# pwr.net
KiCad netlist of a schematic drawn in Altium Designer
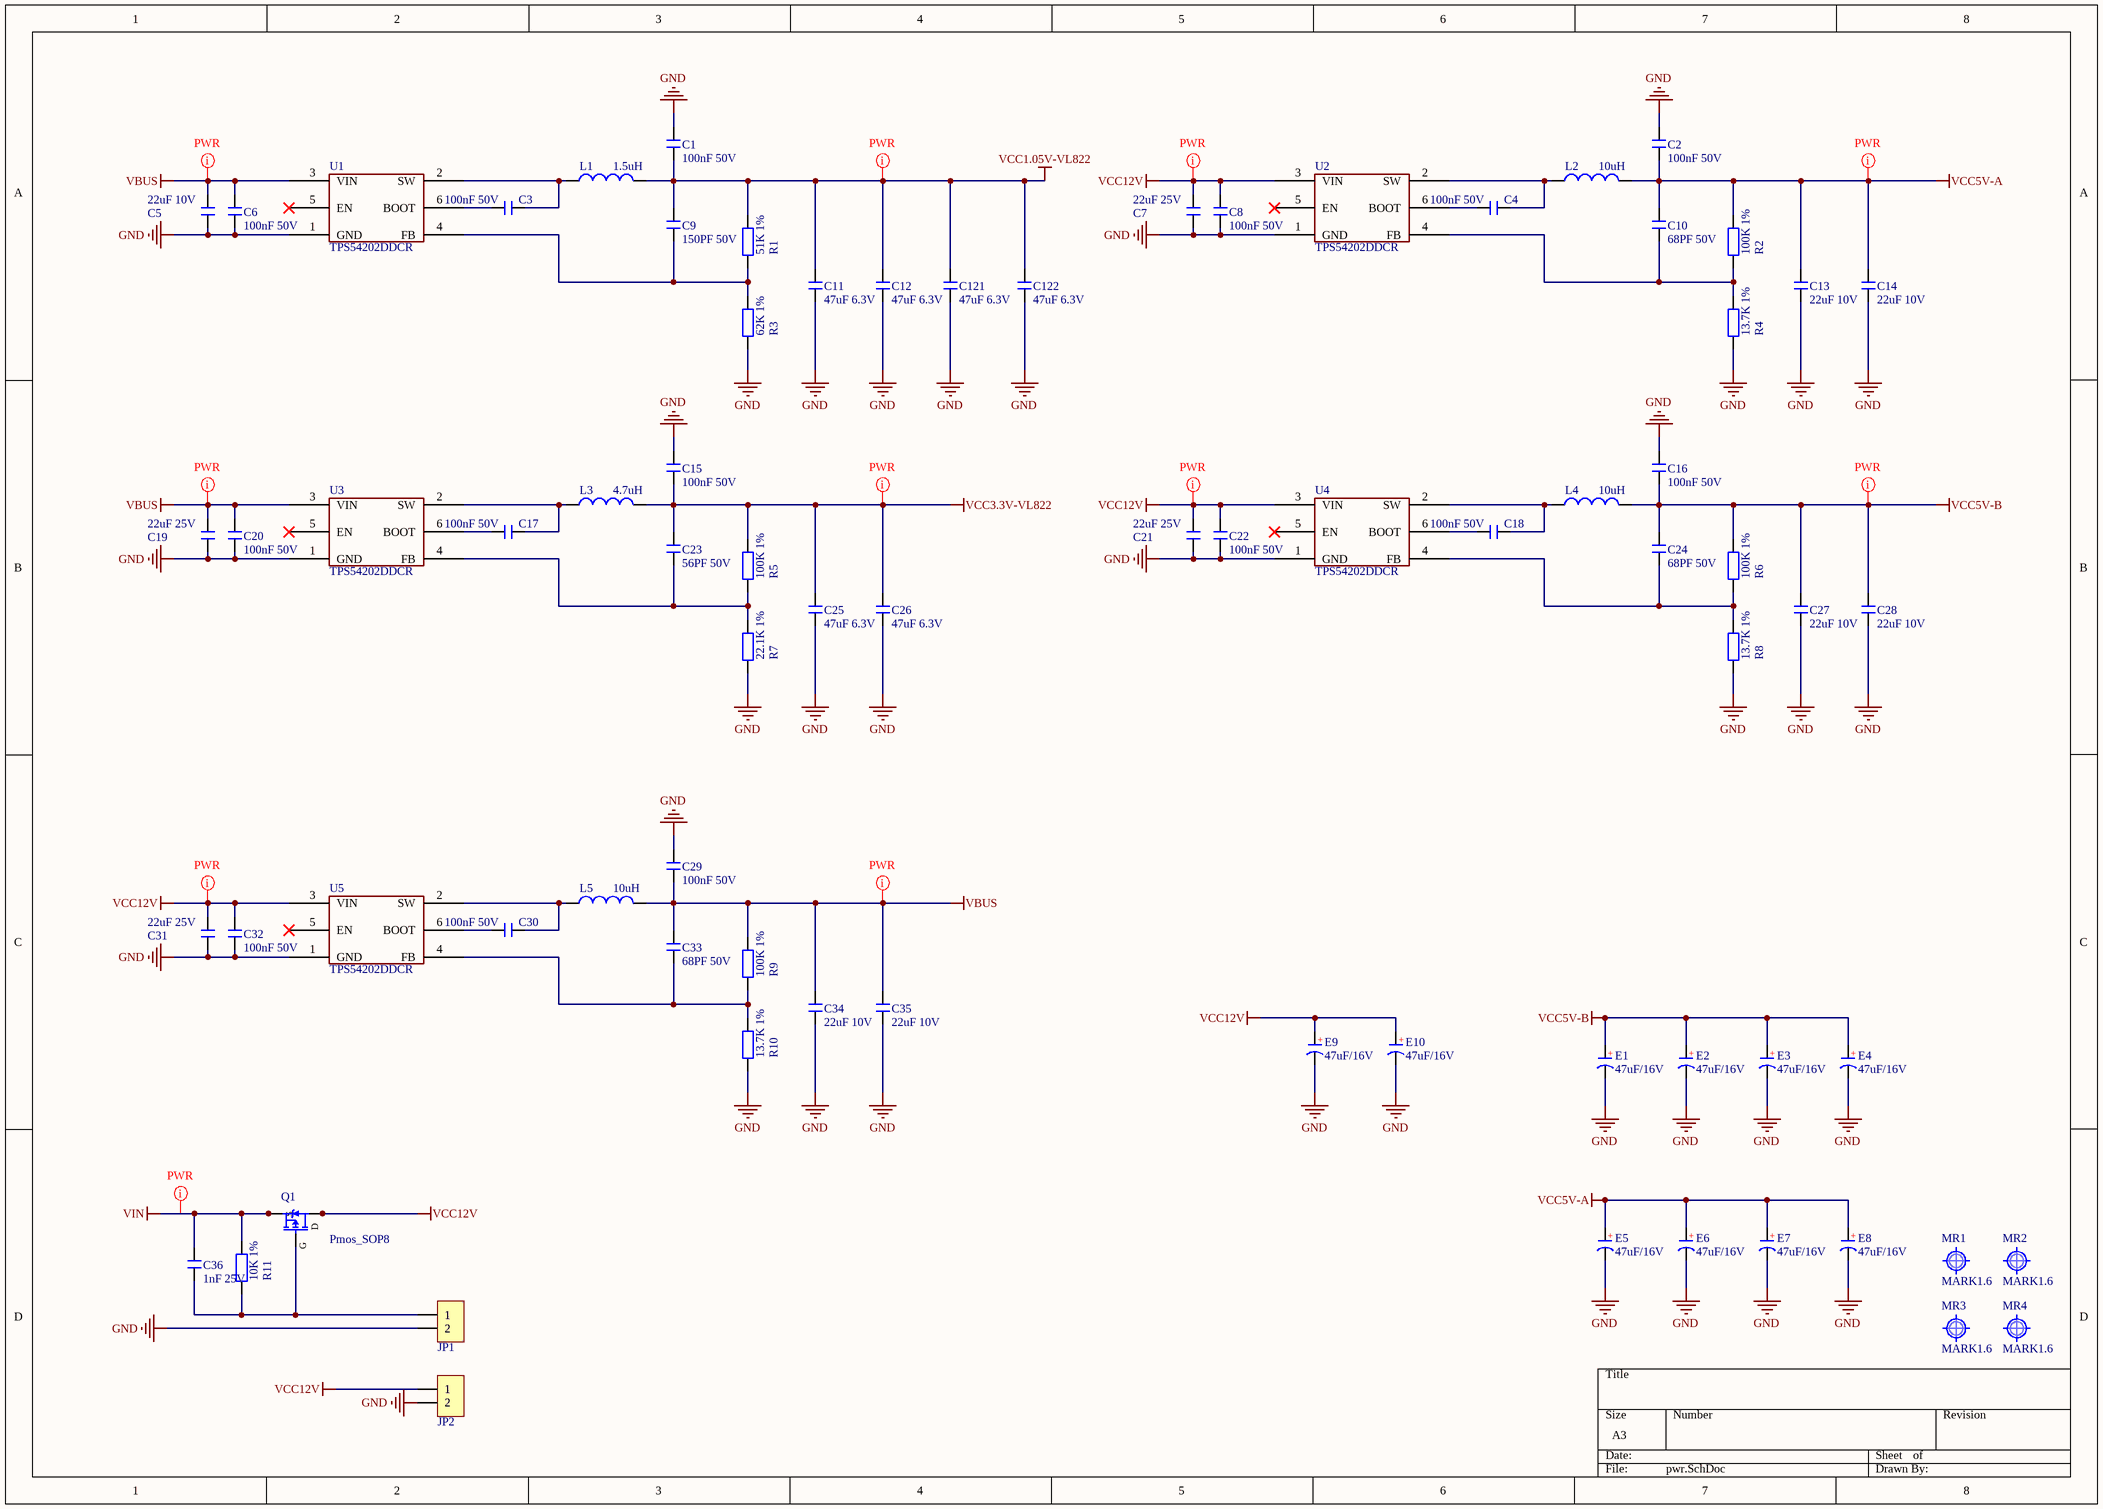
[diagram p0: pwr.SchDoc]

(export (version "E")
  (design (tool "Eeschema 10.0.6"))
  (components
    (comp (ref "C1")
      (value "100nF 50V")
      (footprint "C0402_L")
      (description "无极性贴片电容")
      (fields (field (name "版权归属") "源创客"))
      (libsource (lib "Capacitor") (part "C"))
    )
    (comp (ref "C2")
      (value "100nF 50V")
      (footprint "C0402_L")
      (description "无极性贴片电容")
      (fields (field (name "版权归属") "源创客"))
      (libsource (lib "Capacitor") (part "C"))
    )
    (comp (ref "C3")
      (value "100nF 50V")
      (footprint "C0402_L")
      (description "无极性贴片电容")
      (fields (field (name "版权归属") "源创客"))
      (libsource (lib "Capacitor") (part "C"))
    )
    (comp (ref "C4")
      (value "100nF 50V")
      (footprint "C0402_L")
      (description "无极性贴片电容")
      (fields (field (name "版权归属") "源创客"))
      (libsource (lib "Capacitor") (part "C"))
    )
    (comp (ref "C5")
      (value "22uF 10V")
      (footprint "C0805_L")
      (description "无极性贴片电容")
      (fields (field (name "版权归属") "源创客"))
      (libsource (lib "Capacitor") (part "C"))
    )
    (comp (ref "C6")
      (value "100nF 50V")
      (footprint "C0402_L")
      (description "无极性贴片电容")
      (fields (field (name "版权归属") "源创客"))
      (libsource (lib "Capacitor") (part "C"))
    )
    (comp (ref "C7")
      (value "22uF 25V")
      (footprint "C0805_L")
      (description "无极性贴片电容")
      (fields (field (name "版权归属") "源创客"))
      (libsource (lib "Capacitor") (part "C"))
    )
    (comp (ref "C8")
      (value "100nF 50V")
      (footprint "C0402_L")
      (description "无极性贴片电容")
      (fields (field (name "版权归属") "源创客"))
      (libsource (lib "Capacitor") (part "C"))
    )
    (comp (ref "C9")
      (value "150PF 50V")
      (footprint "C0402_L")
      (description "无极性贴片电容")
      (fields (field (name "版权归属") "源创客"))
      (libsource (lib "Capacitor") (part "C"))
    )
    (comp (ref "C10")
      (value "68PF 50V")
      (footprint "C0402_L")
      (description "无极性贴片电容")
      (fields (field (name "版权归属") "源创客"))
      (libsource (lib "Capacitor") (part "C"))
    )
    (comp (ref "C11")
      (value "47uF 6.3V")
      (footprint "C0805_L")
      (description "无极性贴片电容")
      (fields (field (name "版权归属") "源创客"))
      (libsource (lib "Capacitor") (part "C"))
    )
    (comp (ref "C12")
      (value "47uF 6.3V")
      (footprint "C0805_L")
      (description "无极性贴片电容")
      (fields (field (name "版权归属") "源创客"))
      (libsource (lib "Capacitor") (part "C"))
    )
    (comp (ref "C13")
      (value "22uF 10V")
      (footprint "C0805_L")
      (description "无极性贴片电容")
      (fields (field (name "版权归属") "源创客"))
      (libsource (lib "Capacitor") (part "C"))
    )
    (comp (ref "C14")
      (value "22uF 10V")
      (footprint "C0805_L")
      (description "无极性贴片电容")
      (fields (field (name "版权归属") "源创客"))
      (libsource (lib "Capacitor") (part "C"))
    )
    (comp (ref "C15")
      (value "100nF 50V")
      (footprint "C0402_L")
      (description "无极性贴片电容")
      (fields (field (name "版权归属") "源创客"))
      (libsource (lib "Capacitor") (part "C"))
    )
    (comp (ref "C16")
      (value "100nF 50V")
      (footprint "C0402_L")
      (description "无极性贴片电容")
      (fields (field (name "版权归属") "源创客"))
      (libsource (lib "Capacitor") (part "C"))
    )
    (comp (ref "C17")
      (value "100nF 50V")
      (footprint "C0402_L")
      (description "无极性贴片电容")
      (fields (field (name "版权归属") "源创客"))
      (libsource (lib "Capacitor") (part "C"))
    )
    (comp (ref "C18")
      (value "100nF 50V")
      (footprint "C0402_L")
      (description "无极性贴片电容")
      (fields (field (name "版权归属") "源创客"))
      (libsource (lib "Capacitor") (part "C"))
    )
    (comp (ref "C19")
      (value "22uF 25V")
      (footprint "C0805_L")
      (description "无极性贴片电容")
      (fields (field (name "版权归属") "源创客"))
      (libsource (lib "Capacitor") (part "C"))
    )
    (comp (ref "C20")
      (value "100nF 50V")
      (footprint "C0402_L")
      (description "无极性贴片电容")
      (fields (field (name "版权归属") "源创客"))
      (libsource (lib "Capacitor") (part "C"))
    )
    (comp (ref "C21")
      (value "22uF 25V")
      (footprint "C0805_L")
      (description "无极性贴片电容")
      (fields (field (name "版权归属") "源创客"))
      (libsource (lib "Capacitor") (part "C"))
    )
    (comp (ref "C22")
      (value "100nF 50V")
      (footprint "C0402_L")
      (description "无极性贴片电容")
      (fields (field (name "版权归属") "源创客"))
      (libsource (lib "Capacitor") (part "C"))
    )
    (comp (ref "C23")
      (value "56PF 50V")
      (footprint "C0402_L")
      (description "无极性贴片电容")
      (fields (field (name "版权归属") "源创客"))
      (libsource (lib "Capacitor") (part "C"))
    )
    (comp (ref "C24")
      (value "68PF 50V")
      (footprint "C0402_L")
      (description "无极性贴片电容")
      (fields (field (name "版权归属") "源创客"))
      (libsource (lib "Capacitor") (part "C"))
    )
    (comp (ref "C25")
      (value "47uF 6.3V")
      (footprint "C0805_L")
      (description "无极性贴片电容")
      (fields (field (name "版权归属") "源创客"))
      (libsource (lib "Capacitor") (part "C"))
    )
    (comp (ref "C26")
      (value "47uF 6.3V")
      (footprint "C0805_L")
      (description "无极性贴片电容")
      (fields (field (name "版权归属") "源创客"))
      (libsource (lib "Capacitor") (part "C"))
    )
    (comp (ref "C27")
      (value "22uF 10V")
      (footprint "C0805_L")
      (description "无极性贴片电容")
      (fields (field (name "版权归属") "源创客"))
      (libsource (lib "Capacitor") (part "C"))
    )
    (comp (ref "C28")
      (value "22uF 10V")
      (footprint "C0805_L")
      (description "无极性贴片电容")
      (fields (field (name "版权归属") "源创客"))
      (libsource (lib "Capacitor") (part "C"))
    )
    (comp (ref "C29")
      (value "100nF 50V")
      (footprint "C0402_L")
      (description "无极性贴片电容")
      (fields (field (name "版权归属") "源创客"))
      (libsource (lib "Capacitor") (part "C"))
    )
    (comp (ref "C30")
      (value "100nF 50V")
      (footprint "C0402_L")
      (description "无极性贴片电容")
      (fields (field (name "版权归属") "源创客"))
      (libsource (lib "Capacitor") (part "C"))
    )
    (comp (ref "C31")
      (value "22uF 25V")
      (footprint "C0805_L")
      (description "无极性贴片电容")
      (fields (field (name "版权归属") "源创客"))
      (libsource (lib "Capacitor") (part "C"))
    )
    (comp (ref "C32")
      (value "100nF 50V")
      (footprint "C0402_L")
      (description "无极性贴片电容")
      (fields (field (name "版权归属") "源创客"))
      (libsource (lib "Capacitor") (part "C"))
    )
    (comp (ref "C33")
      (value "68PF 50V")
      (footprint "C0402_L")
      (description "无极性贴片电容")
      (fields (field (name "版权归属") "源创客"))
      (libsource (lib "Capacitor") (part "C"))
    )
    (comp (ref "C34")
      (value "22uF 10V")
      (footprint "C0805_L")
      (description "无极性贴片电容")
      (fields (field (name "版权归属") "源创客"))
      (libsource (lib "Capacitor") (part "C"))
    )
    (comp (ref "C35")
      (value "22uF 10V")
      (footprint "C0805_L")
      (description "无极性贴片电容")
      (fields (field (name "版权归属") "源创客"))
      (libsource (lib "Capacitor") (part "C"))
    )
    (comp (ref "C36")
      (value "1nF 25V")
      (footprint "C0402_L")
      (description "无极性贴片电容")
      (fields (field (name "版权归属") "源创客"))
      (libsource (lib "Capacitor") (part "C"))
    )
    (comp (ref "C121")
      (value "47uF 6.3V")
      (footprint "C0805_L")
      (description "无极性贴片电容")
      (fields (field (name "版权归属") "源创客"))
      (libsource (lib "Capacitor") (part "C"))
    )
    (comp (ref "C122")
      (value "47uF 6.3V")
      (footprint "C0805_L")
      (description "无极性贴片电容")
      (fields (field (name "版权归属") "源创客"))
      (libsource (lib "Capacitor") (part "C"))
    )
    (comp (ref "E1")
      (value "47uF/16V")
      (footprint "CS 6*4 - R")
      (description "贴片电解电容")
      (fields (field (name "版权归属") "源创客"))
      (libsource (lib "Capacitor") (part "C-CD"))
    )
    (comp (ref "E2")
      (value "47uF/16V")
      (footprint "CS 6*4 - R")
      (description "贴片电解电容")
      (fields (field (name "版权归属") "源创客"))
      (libsource (lib "Capacitor") (part "C-CD"))
    )
    (comp (ref "E3")
      (value "47uF/16V")
      (footprint "CS 6*4 - R")
      (description "贴片电解电容")
      (fields (field (name "版权归属") "源创客"))
      (libsource (lib "Capacitor") (part "C-CD"))
    )
    (comp (ref "E4")
      (value "47uF/16V")
      (footprint "CS 6*4 - R")
      (description "贴片电解电容")
      (fields (field (name "版权归属") "源创客"))
      (libsource (lib "Capacitor") (part "C-CD"))
    )
    (comp (ref "E5")
      (value "47uF/16V")
      (footprint "CS 6*4 - R")
      (description "贴片电解电容")
      (fields (field (name "版权归属") "源创客"))
      (libsource (lib "Capacitor") (part "C-CD"))
    )
    (comp (ref "E6")
      (value "47uF/16V")
      (footprint "CS 6*4 - R")
      (description "贴片电解电容")
      (fields (field (name "版权归属") "源创客"))
      (libsource (lib "Capacitor") (part "C-CD"))
    )
    (comp (ref "E7")
      (value "47uF/16V")
      (footprint "CS 6*4 - R")
      (description "贴片电解电容")
      (fields (field (name "版权归属") "源创客"))
      (libsource (lib "Capacitor") (part "C-CD"))
    )
    (comp (ref "E8")
      (value "47uF/16V")
      (footprint "CS 6*4 - R")
      (description "贴片电解电容")
      (fields (field (name "版权归属") "源创客"))
      (libsource (lib "Capacitor") (part "C-CD"))
    )
    (comp (ref "E9")
      (value "47uF/16V")
      (footprint "CS 6*4 - R")
      (description "贴片电解电容")
      (fields (field (name "版权归属") "源创客"))
      (libsource (lib "Capacitor") (part "C-CD"))
    )
    (comp (ref "E10")
      (value "47uF/16V")
      (footprint "CS 6*4 - R")
      (description "贴片电解电容")
      (fields (field (name "版权归属") "源创客"))
      (libsource (lib "Capacitor") (part "C-CD"))
    )
    (comp (ref "JP1")
      (value "HDR-1X2")
      (footprint "ZH1.5-WS-2P")
      (description "2P接插件")
      (fields (field (name "版权归属") "源创客"))
      (libsource (lib "Connector-PinHeader") (part "Header 2"))
    )
    (comp (ref "JP2")
      (value "HDR-1X2")
      (footprint "XH2.54-WS-2P")
      (description "2P接插件")
      (fields (field (name "版权归属") "源创客"))
      (libsource (lib "Connector-PinHeader") (part "Header 2"))
    )
    (comp (ref "L1")
      (value "1.5uH")
      (footprint "SMMS0420")
      (description "小功率贴片电感")
      (fields (field (name "版权归属") "源创客"))
      (libsource (lib "Inductor") (part "L"))
    )
    (comp (ref "L2")
      (value "10uH")
      (footprint "SMMS0420")
      (description "小功率贴片电感")
      (fields (field (name "版权归属") "源创客"))
      (libsource (lib "Inductor") (part "L"))
    )
    (comp (ref "L3")
      (value "4.7uH")
      (footprint "SMMS0420")
      (description "小功率贴片电感")
      (fields (field (name "版权归属") "源创客"))
      (libsource (lib "Inductor") (part "L"))
    )
    (comp (ref "L4")
      (value "10uH")
      (footprint "SMMS0420")
      (description "小功率贴片电感")
      (fields (field (name "版权归属") "源创客"))
      (libsource (lib "Inductor") (part "L"))
    )
    (comp (ref "L5")
      (value "10uH")
      (footprint "SMMS0420")
      (description "小功率贴片电感")
      (fields (field (name "版权归属") "源创客"))
      (libsource (lib "Inductor") (part "L"))
    )
    (comp (ref "MR1")
      (value "MARK1.6")
      (footprint "Mark 1")
      (description "光学定位点")
      (fields (field (name "版权归属") "源创客"))
      (libsource (lib "Hole") (part "MARK"))
    )
    (comp (ref "MR2")
      (value "MARK1.6")
      (footprint "Mark 1")
      (description "光学定位点")
      (fields (field (name "版权归属") "源创客"))
      (libsource (lib "Hole") (part "MARK"))
    )
    (comp (ref "MR3")
      (value "MARK1.6")
      (footprint "Mark 1")
      (description "光学定位点")
      (fields (field (name "版权归属") "源创客"))
      (libsource (lib "Hole") (part "MARK"))
    )
    (comp (ref "MR4")
      (value "MARK1.6")
      (footprint "Mark 1")
      (description "光学定位点")
      (fields (field (name "版权归属") "源创客"))
      (libsource (lib "Hole") (part "MARK"))
    )
    (comp (ref "Q1")
      (value "Pmos_SOP8")
      (footprint "SOP8_L")
      (fields (field (name "版权归属") "源创客"))
      (libsource (lib "MOSFET BJT IGBT") (part "Pmos_SOP8"))
    )
    (comp (ref "R1")
      (value "51K 1%")
      (footprint "R0402_L")
      (description "贴片电阻")
      (fields (field (name "版权归属") "源创客"))
      (libsource (lib "Resistor") (part "R"))
    )
    (comp (ref "R2")
      (value "100K 1%")
      (footprint "R0402_L")
      (description "贴片电阻")
      (fields (field (name "版权归属") "源创客"))
      (libsource (lib "Resistor") (part "R"))
    )
    (comp (ref "R3")
      (value "62K 1%")
      (footprint "R0402_L")
      (description "贴片电阻")
      (fields (field (name "版权归属") "源创客"))
      (libsource (lib "Resistor") (part "R"))
    )
    (comp (ref "R4")
      (value "13.7K 1%")
      (footprint "R0402_L")
      (description "贴片电阻")
      (fields (field (name "版权归属") "源创客"))
      (libsource (lib "Resistor") (part "R"))
    )
    (comp (ref "R5")
      (value "100K 1%")
      (footprint "R0402_L")
      (description "贴片电阻")
      (fields (field (name "版权归属") "源创客"))
      (libsource (lib "Resistor") (part "R"))
    )
    (comp (ref "R6")
      (value "100K 1%")
      (footprint "R0402_L")
      (description "贴片电阻")
      (fields (field (name "版权归属") "源创客"))
      (libsource (lib "Resistor") (part "R"))
    )
    (comp (ref "R7")
      (value "22.1K 1%")
      (footprint "R0402_L")
      (description "贴片电阻")
      (fields (field (name "版权归属") "源创客"))
      (libsource (lib "Resistor") (part "R"))
    )
    (comp (ref "R8")
      (value "13.7K 1%")
      (footprint "R0402_L")
      (description "贴片电阻")
      (fields (field (name "版权归属") "源创客"))
      (libsource (lib "Resistor") (part "R"))
    )
    (comp (ref "R9")
      (value "100K 1%")
      (footprint "R0402_L")
      (description "贴片电阻")
      (fields (field (name "版权归属") "源创客"))
      (libsource (lib "Resistor") (part "R"))
    )
    (comp (ref "R10")
      (value "13.7K 1%")
      (footprint "R0402_L")
      (description "贴片电阻")
      (fields (field (name "版权归属") "源创客"))
      (libsource (lib "Resistor") (part "R"))
    )
    (comp (ref "R11")
      (value "10K 1%")
      (footprint "R0402_L")
      (description "贴片电阻")
      (fields (field (name "版权归属") "源创客"))
      (libsource (lib "Resistor") (part "R"))
    )
    (comp (ref "U1")
      (value "TPS54202DDCR")
      (footprint "SOT23-6L")
      (description "DCDC Convert")
      (libsource (lib "DCDC Convert") (part "TPS54202DDCR"))
    )
    (comp (ref "U2")
      (value "TPS54202DDCR")
      (footprint "SOT23-6L")
      (description "DCDC Convert")
      (libsource (lib "DCDC Convert") (part "TPS54202DDCR"))
    )
    (comp (ref "U3")
      (value "TPS54202DDCR")
      (footprint "SOT23-6L")
      (description "DCDC Convert")
      (libsource (lib "DCDC Convert") (part "TPS54202DDCR"))
    )
    (comp (ref "U4")
      (value "TPS54202DDCR")
      (footprint "SOT23-6L")
      (description "DCDC Convert")
      (libsource (lib "DCDC Convert") (part "TPS54202DDCR"))
    )
    (comp (ref "U5")
      (value "TPS54202DDCR")
      (footprint "SOT23-6L")
      (description "DCDC Convert")
      (libsource (lib "DCDC Convert") (part "TPS54202DDCR"))
    )
  )
  (nets
    (net (code "1") (name "GND") (class "Default")
      (node (ref "C1") (pin "2") (pinfunction "2_2") (pintype "passive"))
      (node (ref "C11") (pin "2") (pinfunction "2_2") (pintype "passive"))
      (node (ref "C12") (pin "2") (pinfunction "2_2") (pintype "passive"))
      (node (ref "C121") (pin "2") (pinfunction "2_2") (pintype "passive"))
      (node (ref "C122") (pin "2") (pinfunction "2_2") (pintype "passive"))
      (node (ref "C13") (pin "2") (pinfunction "2_2") (pintype "passive"))
      (node (ref "C14") (pin "2") (pinfunction "2_2") (pintype "passive"))
      (node (ref "C15") (pin "2") (pinfunction "2_2") (pintype "passive"))
      (node (ref "C16") (pin "2") (pinfunction "2_2") (pintype "passive"))
      (node (ref "C19") (pin "1") (pinfunction "1_1") (pintype "passive"))
      (node (ref "C2") (pin "2") (pinfunction "2_2") (pintype "passive"))
      (node (ref "C20") (pin "1") (pinfunction "1_1") (pintype "passive"))
      (node (ref "C21") (pin "1") (pinfunction "1_1") (pintype "passive"))
      (node (ref "C22") (pin "1") (pinfunction "1_1") (pintype "passive"))
      (node (ref "C25") (pin "2") (pinfunction "2_2") (pintype "passive"))
      (node (ref "C26") (pin "2") (pinfunction "2_2") (pintype "passive"))
      (node (ref "C27") (pin "2") (pinfunction "2_2") (pintype "passive"))
      (node (ref "C28") (pin "2") (pinfunction "2_2") (pintype "passive"))
      (node (ref "C29") (pin "2") (pinfunction "2_2") (pintype "passive"))
      (node (ref "C31") (pin "1") (pinfunction "1_1") (pintype "passive"))
      (node (ref "C32") (pin "1") (pinfunction "1_1") (pintype "passive"))
      (node (ref "C34") (pin "2") (pinfunction "2_2") (pintype "passive"))
      (node (ref "C35") (pin "2") (pinfunction "2_2") (pintype "passive"))
      (node (ref "C5") (pin "1") (pinfunction "1_1") (pintype "passive"))
      (node (ref "C6") (pin "1") (pinfunction "1_1") (pintype "passive"))
      (node (ref "C7") (pin "1") (pinfunction "1_1") (pintype "passive"))
      (node (ref "C8") (pin "1") (pinfunction "1_1") (pintype "passive"))
      (node (ref "E1") (pin "2") (pinfunction "K_2") (pintype "passive"))
      (node (ref "E10") (pin "2") (pinfunction "K_2") (pintype "passive"))
      (node (ref "E2") (pin "2") (pinfunction "K_2") (pintype "passive"))
      (node (ref "E3") (pin "2") (pinfunction "K_2") (pintype "passive"))
      (node (ref "E4") (pin "2") (pinfunction "K_2") (pintype "passive"))
      (node (ref "E5") (pin "2") (pinfunction "K_2") (pintype "passive"))
      (node (ref "E6") (pin "2") (pinfunction "K_2") (pintype "passive"))
      (node (ref "E7") (pin "2") (pinfunction "K_2") (pintype "passive"))
      (node (ref "E8") (pin "2") (pinfunction "K_2") (pintype "passive"))
      (node (ref "E9") (pin "2") (pinfunction "K_2") (pintype "passive"))
      (node (ref "JP1") (pin "2") (pinfunction "2_2") (pintype "passive"))
      (node (ref "JP2") (pin "2") (pinfunction "2_2") (pintype "passive"))
      (node (ref "R10") (pin "2") (pinfunction "2_2") (pintype "passive"))
      (node (ref "R3") (pin "2") (pinfunction "2_2") (pintype "passive"))
      (node (ref "R4") (pin "2") (pinfunction "2_2") (pintype "passive"))
      (node (ref "R7") (pin "2") (pinfunction "2_2") (pintype "passive"))
      (node (ref "R8") (pin "2") (pinfunction "2_2") (pintype "passive"))
      (node (ref "U1") (pin "1") (pinfunction "GND_1") (pintype "passive"))
      (node (ref "U2") (pin "1") (pinfunction "GND_1") (pintype "passive"))
      (node (ref "U3") (pin "1") (pinfunction "GND_1") (pintype "passive"))
      (node (ref "U4") (pin "1") (pinfunction "GND_1") (pintype "passive"))
      (node (ref "U5") (pin "1") (pinfunction "GND_1") (pintype "passive"))
    )
    (net (code "2") (name "Net-(Q1-G)") (class "Default")
      (node (ref "C36") (pin "2") (pinfunction "2_2") (pintype "passive"))
      (node (ref "JP1") (pin "1") (pinfunction "1_1") (pintype "passive"))
      (node (ref "Q1") (pin "4") (pinfunction "G_4") (pintype "passive"))
      (node (ref "R11") (pin "2") (pinfunction "2_2") (pintype "passive"))
    )
    (net (code "3") (name "Net-(U1-BOOT)") (class "Default")
      (node (ref "C3") (pin "1") (pinfunction "1_1") (pintype "passive"))
      (node (ref "U1") (pin "6") (pinfunction "BOOT_6") (pintype "passive"))
    )
    (net (code "4") (name "Net-(U1-FB)") (class "Default")
      (node (ref "C9") (pin "1") (pinfunction "1_1") (pintype "passive"))
      (node (ref "R1") (pin "2") (pinfunction "2_2") (pintype "passive"))
      (node (ref "R3") (pin "1") (pinfunction "1_1") (pintype "passive"))
      (node (ref "U1") (pin "4") (pinfunction "FB_4") (pintype "passive"))
    )
    (net (code "5") (name "Net-(U1-SW)") (class "Default")
      (node (ref "C3") (pin "2") (pinfunction "2_2") (pintype "passive"))
      (node (ref "L1") (pin "1") (pinfunction "1_1") (pintype "passive"))
      (node (ref "U1") (pin "2") (pinfunction "SW_2") (pintype "passive"))
    )
    (net (code "6") (name "Net-(U2-BOOT)") (class "Default")
      (node (ref "C4") (pin "1") (pinfunction "1_1") (pintype "passive"))
      (node (ref "U2") (pin "6") (pinfunction "BOOT_6") (pintype "passive"))
    )
    (net (code "7") (name "Net-(U2-FB)") (class "Default")
      (node (ref "C10") (pin "1") (pinfunction "1_1") (pintype "passive"))
      (node (ref "R2") (pin "2") (pinfunction "2_2") (pintype "passive"))
      (node (ref "R4") (pin "1") (pinfunction "1_1") (pintype "passive"))
      (node (ref "U2") (pin "4") (pinfunction "FB_4") (pintype "passive"))
    )
    (net (code "8") (name "Net-(U2-SW)") (class "Default")
      (node (ref "C4") (pin "2") (pinfunction "2_2") (pintype "passive"))
      (node (ref "L2") (pin "1") (pinfunction "1_1") (pintype "passive"))
      (node (ref "U2") (pin "2") (pinfunction "SW_2") (pintype "passive"))
    )
    (net (code "9") (name "Net-(U3-BOOT)") (class "Default")
      (node (ref "C17") (pin "1") (pinfunction "1_1") (pintype "passive"))
      (node (ref "U3") (pin "6") (pinfunction "BOOT_6") (pintype "passive"))
    )
    (net (code "10") (name "Net-(U3-FB)") (class "Default")
      (node (ref "C23") (pin "1") (pinfunction "1_1") (pintype "passive"))
      (node (ref "R5") (pin "2") (pinfunction "2_2") (pintype "passive"))
      (node (ref "R7") (pin "1") (pinfunction "1_1") (pintype "passive"))
      (node (ref "U3") (pin "4") (pinfunction "FB_4") (pintype "passive"))
    )
    (net (code "11") (name "Net-(U3-SW)") (class "Default")
      (node (ref "C17") (pin "2") (pinfunction "2_2") (pintype "passive"))
      (node (ref "L3") (pin "1") (pinfunction "1_1") (pintype "passive"))
      (node (ref "U3") (pin "2") (pinfunction "SW_2") (pintype "passive"))
    )
    (net (code "12") (name "Net-(U4-BOOT)") (class "Default")
      (node (ref "C18") (pin "1") (pinfunction "1_1") (pintype "passive"))
      (node (ref "U4") (pin "6") (pinfunction "BOOT_6") (pintype "passive"))
    )
    (net (code "13") (name "Net-(U4-FB)") (class "Default")
      (node (ref "C24") (pin "1") (pinfunction "1_1") (pintype "passive"))
      (node (ref "R6") (pin "2") (pinfunction "2_2") (pintype "passive"))
      (node (ref "R8") (pin "1") (pinfunction "1_1") (pintype "passive"))
      (node (ref "U4") (pin "4") (pinfunction "FB_4") (pintype "passive"))
    )
    (net (code "14") (name "Net-(U4-SW)") (class "Default")
      (node (ref "C18") (pin "2") (pinfunction "2_2") (pintype "passive"))
      (node (ref "L4") (pin "1") (pinfunction "1_1") (pintype "passive"))
      (node (ref "U4") (pin "2") (pinfunction "SW_2") (pintype "passive"))
    )
    (net (code "15") (name "Net-(U5-BOOT)") (class "Default")
      (node (ref "C30") (pin "1") (pinfunction "1_1") (pintype "passive"))
      (node (ref "U5") (pin "6") (pinfunction "BOOT_6") (pintype "passive"))
    )
    (net (code "16") (name "Net-(U5-FB)") (class "Default")
      (node (ref "C33") (pin "1") (pinfunction "1_1") (pintype "passive"))
      (node (ref "R10") (pin "1") (pinfunction "1_1") (pintype "passive"))
      (node (ref "R9") (pin "2") (pinfunction "2_2") (pintype "passive"))
      (node (ref "U5") (pin "4") (pinfunction "FB_4") (pintype "passive"))
    )
    (net (code "17") (name "Net-(U5-SW)") (class "Default")
      (node (ref "C30") (pin "2") (pinfunction "2_2") (pintype "passive"))
      (node (ref "L5") (pin "1") (pinfunction "1_1") (pintype "passive"))
      (node (ref "U5") (pin "2") (pinfunction "SW_2") (pintype "passive"))
    )
    (net (code "18") (name "VBUS") (class "Default")
      (node (ref "C19") (pin "2") (pinfunction "2_2") (pintype "passive"))
      (node (ref "C20") (pin "2") (pinfunction "2_2") (pintype "passive"))
      (node (ref "C29") (pin "1") (pinfunction "1_1") (pintype "passive"))
      (node (ref "C33") (pin "2") (pinfunction "2_2") (pintype "passive"))
      (node (ref "C34") (pin "1") (pinfunction "1_1") (pintype "passive"))
      (node (ref "C35") (pin "1") (pinfunction "1_1") (pintype "passive"))
      (node (ref "C5") (pin "2") (pinfunction "2_2") (pintype "passive"))
      (node (ref "C6") (pin "2") (pinfunction "2_2") (pintype "passive"))
      (node (ref "L5") (pin "2") (pinfunction "2_2") (pintype "passive"))
      (node (ref "R9") (pin "1") (pinfunction "1_1") (pintype "passive"))
      (node (ref "U1") (pin "3") (pinfunction "VIN_3") (pintype "passive"))
      (node (ref "U3") (pin "3") (pinfunction "VIN_3") (pintype "passive"))
    )
    (net (code "19") (name "VCC1.05V-VL822") (class "Default")
      (node (ref "C1") (pin "1") (pinfunction "1_1") (pintype "passive"))
      (node (ref "C11") (pin "1") (pinfunction "1_1") (pintype "passive"))
      (node (ref "C12") (pin "1") (pinfunction "1_1") (pintype "passive"))
      (node (ref "C121") (pin "1") (pinfunction "1_1") (pintype "passive"))
      (node (ref "C122") (pin "1") (pinfunction "1_1") (pintype "passive"))
      (node (ref "C9") (pin "2") (pinfunction "2_2") (pintype "passive"))
      (node (ref "L1") (pin "2") (pinfunction "2_2") (pintype "passive"))
      (node (ref "R1") (pin "1") (pinfunction "1_1") (pintype "passive"))
    )
    (net (code "20") (name "VCC3.3V-VL822") (class "Default")
      (node (ref "C15") (pin "1") (pinfunction "1_1") (pintype "passive"))
      (node (ref "C23") (pin "2") (pinfunction "2_2") (pintype "passive"))
      (node (ref "C25") (pin "1") (pinfunction "1_1") (pintype "passive"))
      (node (ref "C26") (pin "1") (pinfunction "1_1") (pintype "passive"))
      (node (ref "L3") (pin "2") (pinfunction "2_2") (pintype "passive"))
      (node (ref "R5") (pin "1") (pinfunction "1_1") (pintype "passive"))
    )
    (net (code "21") (name "VCC5V-A") (class "Default")
      (node (ref "C10") (pin "2") (pinfunction "2_2") (pintype "passive"))
      (node (ref "C13") (pin "1") (pinfunction "1_1") (pintype "passive"))
      (node (ref "C14") (pin "1") (pinfunction "1_1") (pintype "passive"))
      (node (ref "C2") (pin "1") (pinfunction "1_1") (pintype "passive"))
      (node (ref "E5") (pin "1") (pinfunction "A_1") (pintype "passive"))
      (node (ref "E6") (pin "1") (pinfunction "A_1") (pintype "passive"))
      (node (ref "E7") (pin "1") (pinfunction "A_1") (pintype "passive"))
      (node (ref "E8") (pin "1") (pinfunction "A_1") (pintype "passive"))
      (node (ref "L2") (pin "2") (pinfunction "2_2") (pintype "passive"))
      (node (ref "R2") (pin "1") (pinfunction "1_1") (pintype "passive"))
    )
    (net (code "22") (name "VCC5V-B") (class "Default")
      (node (ref "C16") (pin "1") (pinfunction "1_1") (pintype "passive"))
      (node (ref "C24") (pin "2") (pinfunction "2_2") (pintype "passive"))
      (node (ref "C27") (pin "1") (pinfunction "1_1") (pintype "passive"))
      (node (ref "C28") (pin "1") (pinfunction "1_1") (pintype "passive"))
      (node (ref "E1") (pin "1") (pinfunction "A_1") (pintype "passive"))
      (node (ref "E2") (pin "1") (pinfunction "A_1") (pintype "passive"))
      (node (ref "E3") (pin "1") (pinfunction "A_1") (pintype "passive"))
      (node (ref "E4") (pin "1") (pinfunction "A_1") (pintype "passive"))
      (node (ref "L4") (pin "2") (pinfunction "2_2") (pintype "passive"))
      (node (ref "R6") (pin "1") (pinfunction "1_1") (pintype "passive"))
    )
    (net (code "23") (name "VCC12V") (class "Default")
      (node (ref "C21") (pin "2") (pinfunction "2_2") (pintype "passive"))
      (node (ref "C22") (pin "2") (pinfunction "2_2") (pintype "passive"))
      (node (ref "C31") (pin "2") (pinfunction "2_2") (pintype "passive"))
      (node (ref "C32") (pin "2") (pinfunction "2_2") (pintype "passive"))
      (node (ref "C7") (pin "2") (pinfunction "2_2") (pintype "passive"))
      (node (ref "C8") (pin "2") (pinfunction "2_2") (pintype "passive"))
      (node (ref "E10") (pin "1") (pinfunction "A_1") (pintype "passive"))
      (node (ref "E9") (pin "1") (pinfunction "A_1") (pintype "passive"))
      (node (ref "JP2") (pin "1") (pinfunction "1_1") (pintype "passive"))
      (node (ref "Q1") (pin "5") (pinfunction "D_5") (pintype "passive"))
      (node (ref "Q1") (pin "6") (pinfunction "D_6") (pintype "passive"))
      (node (ref "Q1") (pin "7") (pinfunction "D_7") (pintype "passive"))
      (node (ref "Q1") (pin "8") (pinfunction "D_8") (pintype "passive"))
      (node (ref "U2") (pin "3") (pinfunction "VIN_3") (pintype "passive"))
      (node (ref "U4") (pin "3") (pinfunction "VIN_3") (pintype "passive"))
      (node (ref "U5") (pin "3") (pinfunction "VIN_3") (pintype "passive"))
    )
    (net (code "24") (name "VIN") (class "Default")
      (node (ref "C36") (pin "1") (pinfunction "1_1") (pintype "passive"))
      (node (ref "Q1") (pin "1") (pinfunction "S_1") (pintype "passive"))
      (node (ref "Q1") (pin "2") (pinfunction "S_2") (pintype "passive"))
      (node (ref "Q1") (pin "3") (pinfunction "S_3") (pintype "passive"))
      (node (ref "R11") (pin "1") (pinfunction "1_1") (pintype "passive"))
    )
    (net (code "25") (name "unconnected-(U1-EN-Pad5)") (class "Default")
      (node (ref "U1") (pin "5") (pinfunction "EN_5") (pintype "passive+no_connect"))
    )
    (net (code "26") (name "unconnected-(U2-EN-Pad5)") (class "Default")
      (node (ref "U2") (pin "5") (pinfunction "EN_5") (pintype "passive+no_connect"))
    )
    (net (code "27") (name "unconnected-(U3-EN-Pad5)") (class "Default")
      (node (ref "U3") (pin "5") (pinfunction "EN_5") (pintype "passive+no_connect"))
    )
    (net (code "28") (name "unconnected-(U4-EN-Pad5)") (class "Default")
      (node (ref "U4") (pin "5") (pinfunction "EN_5") (pintype "passive+no_connect"))
    )
    (net (code "29") (name "unconnected-(U5-EN-Pad5)") (class "Default")
      (node (ref "U5") (pin "5") (pinfunction "EN_5") (pintype "passive+no_connect"))
    )
  )
)
